# ADC_Buffer.net
KiCad netlist of a schematic drawn in Altium Designer
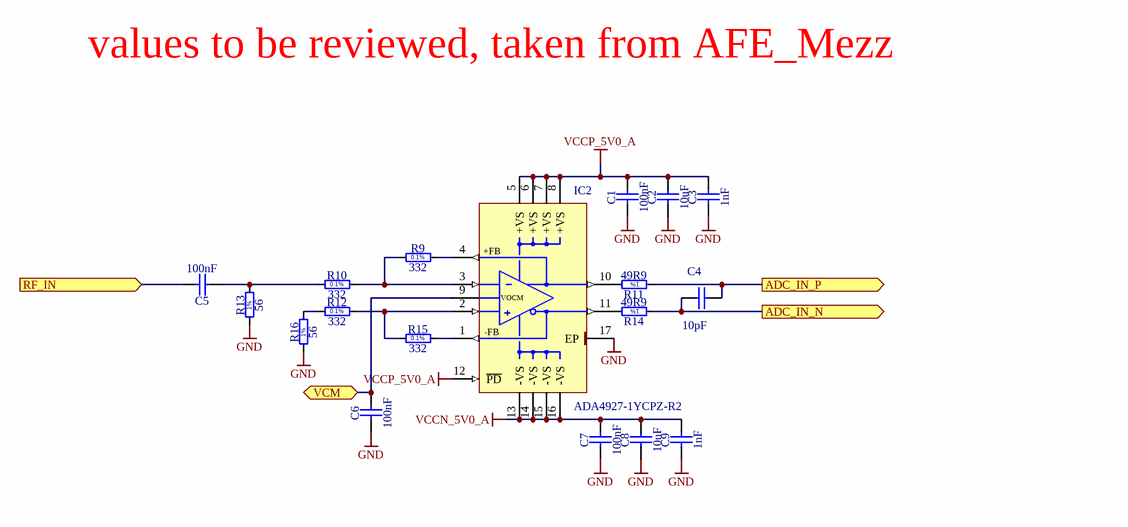
[diagram p0: ADC_Buffer.SchDoc]

(export (version "E")
  (design (tool "Eeschema 10.0.6"))
  (components
    (comp (ref "C1")
      (value "100nF")
      (footprint "CAPC1005X55N")
      (description "Non-polarised capacitor")
      (fields
        (field (name "PART NUMBER") "CC0402_100NF_16V_10%_X5R")
        (field (name "VOLTAGE") "16V")
        (field (name "AUTHOR") "CERN DEM JLC")
      )
      (libsource (lib "Capacitors") (part "Capacitor - non polarized"))
    )
    (comp (ref "C2")
      (value "10uF")
      (footprint "CAPC1608X87N")
      (description "Non-polarised capacitor")
      (fields
        (field (name "PART NUMBER") "CC0603_10UF_6.3V_20%_X5R")
        (field (name "VOLTAGE") "6.3V")
        (field (name "AUTHOR") "CERN DEM JLC")
      )
      (libsource (lib "Capacitors") (part "Capacitor - non polarized"))
    )
    (comp (ref "C3")
      (value "1nF")
      (footprint "CAPC1005X55N")
      (description "Non-polarised capacitor")
      (fields
        (field (name "PART NUMBER") "CC0402_1NF_50V_10%_X7R")
        (field (name "VOLTAGE") "50V")
        (field (name "AUTHOR") "CERN DEM JLC")
      )
      (libsource (lib "Capacitors") (part "Capacitor - non polarized"))
    )
    (comp (ref "C4")
      (value "10pF")
      (footprint "CAPC1608X87N")
      (description "Non-polarised capacitor")
      (fields
        (field (name "PART NUMBER") "CC0603_10PF_50V_5%_NP0")
        (field (name "VOLTAGE") "50V")
        (field (name "AUTHOR") "CERN DEM JLC")
      )
      (libsource (lib "Capacitors") (part "Capacitor - non polarized"))
    )
    (comp (ref "C5")
      (value "100nF")
      (footprint "CAPC1005X55N")
      (description "Non-polarised capacitor")
      (fields
        (field (name "PART NUMBER") "CC0402_100NF_16V_10%_X5R")
        (field (name "VOLTAGE") "16V")
        (field (name "AUTHOR") "CERN DEM JLC")
      )
      (libsource (lib "Capacitors") (part "Capacitor - non polarized"))
    )
    (comp (ref "C6")
      (value "100nF")
      (footprint "CAPC1005X55N")
      (description "Non-polarised capacitor")
      (fields
        (field (name "PART NUMBER") "CC0402_100NF_16V_10%_X5R")
        (field (name "VOLTAGE") "16V")
        (field (name "AUTHOR") "CERN DEM JLC")
      )
      (libsource (lib "Capacitors") (part "Capacitor - non polarized"))
    )
    (comp (ref "C7")
      (value "100nF")
      (footprint "CAPC1005X55N")
      (description "Non-polarised capacitor")
      (fields
        (field (name "PART NUMBER") "CC0402_100NF_16V_10%_X5R")
        (field (name "VOLTAGE") "16V")
        (field (name "AUTHOR") "CERN DEM JLC")
      )
      (libsource (lib "Capacitors") (part "Capacitor - non polarized"))
    )
    (comp (ref "C8")
      (value "10uF")
      (footprint "CAPC1608X87N")
      (description "Non-polarised capacitor")
      (fields
        (field (name "PART NUMBER") "CC0603_10UF_6.3V_20%_X5R")
        (field (name "VOLTAGE") "6.3V")
        (field (name "AUTHOR") "CERN DEM JLC")
      )
      (libsource (lib "Capacitors") (part "Capacitor - non polarized"))
    )
    (comp (ref "C9")
      (value "1nF")
      (footprint "CAPC1005X55N")
      (description "Non-polarised capacitor")
      (fields
        (field (name "PART NUMBER") "CC0402_1NF_50V_10%_X7R")
        (field (name "VOLTAGE") "50V")
        (field (name "AUTHOR") "CERN DEM JLC")
      )
      (libsource (lib "Capacitors") (part "Capacitor - non polarized"))
    )
    (comp (ref "IC2")
      (value "ADA4927-1YCPZ-R2")
      (footprint "QFN50P300X300X100-17N-S145")
      (description "Ultralow Distortion Current Feedback Differential ADC Driver")
      (fields (field (name "MANUFACTURER") "ANALOG DEVICES") (field (name "AUTHOR") "CERN DEM JLC"))
      (libsource (lib "ICs And Semiconductors") (part "ADA4927-1"))
    )
    (comp (ref "R9")
      (value "332")
      (footprint "RESC1608X55N")
      (description "Resistor - 0.1%")
      (fields
        (field (name "PART NUMBER") "R0603_332R_0.1%_0.063W_10PPM")
        (field (name "POWER") "0.063W")
        (field (name "AUTHOR") "CERN DEM JLC")
      )
      (libsource (lib "Resistors") (part "Resistor - 0.1%"))
    )
    (comp (ref "R10")
      (value "332")
      (footprint "RESC1608X55N")
      (description "Resistor - 0.1%")
      (fields
        (field (name "PART NUMBER") "R0603_332R_0.1%_0.063W_10PPM")
        (field (name "POWER") "0.063W")
        (field (name "AUTHOR") "CERN DEM JLC")
      )
      (libsource (lib "Resistors") (part "Resistor - 0.1%"))
    )
    (comp (ref "R11")
      (value "49R9")
      (footprint "RESC1005X40N")
      (description "Resistor - 1%")
      (fields
        (field (name "PART NUMBER") "R0402_49R9_1%_0.0625W_100PPM")
        (field (name "POWER") "0.0625W")
        (field (name "AUTHOR") "CERN DEM JLC")
      )
      (libsource (lib "Resistors") (part "Resistor - 1%"))
    )
    (comp (ref "R12")
      (value "332")
      (footprint "RESC1608X55N")
      (description "Resistor - 0.1%")
      (fields
        (field (name "PART NUMBER") "R0603_332R_0.1%_0.063W_10PPM")
        (field (name "POWER") "0.063W")
        (field (name "AUTHOR") "CERN DEM JLC")
      )
      (libsource (lib "Resistors") (part "Resistor - 0.1%"))
    )
    (comp (ref "R13")
      (value "56")
      (footprint "RESC1005X40N")
      (description "Resistor - 1%")
      (fields
        (field (name "PART NUMBER") "R0402_56R_1%_0.0625W_100PPM")
        (field (name "POWER") "0.0625W")
        (field (name "AUTHOR") "CERN DEM JLC")
      )
      (libsource (lib "Resistors") (part "Resistor - 1%"))
    )
    (comp (ref "R14")
      (value "49R9")
      (footprint "RESC1005X40N")
      (description "Resistor - 1%")
      (fields
        (field (name "PART NUMBER") "R0402_49R9_1%_0.0625W_100PPM")
        (field (name "POWER") "0.0625W")
        (field (name "AUTHOR") "CERN DEM JLC")
      )
      (libsource (lib "Resistors") (part "Resistor - 1%"))
    )
    (comp (ref "R15")
      (value "332")
      (footprint "RESC1608X55N")
      (description "Resistor - 0.1%")
      (fields
        (field (name "PART NUMBER") "R0603_332R_0.1%_0.063W_10PPM")
        (field (name "POWER") "0.063W")
        (field (name "AUTHOR") "CERN DEM JLC")
      )
      (libsource (lib "Resistors") (part "Resistor - 0.1%"))
    )
    (comp (ref "R16")
      (value "56")
      (footprint "RESC1005X40N")
      (description "Resistor - 1%")
      (fields
        (field (name "PART NUMBER") "R0402_56R_1%_0.0625W_100PPM")
        (field (name "POWER") "0.0625W")
        (field (name "AUTHOR") "CERN DEM JLC")
      )
      (libsource (lib "Resistors") (part "Resistor - 1%"))
    )
  )
  (nets
    (net (code "1") (name "/ADC_IN_N") (class "Default")
      (node (ref "C4") (pin "1") (pinfunction "1_1") (pintype "passive"))
      (node (ref "R14") (pin "1") (pinfunction "1_1") (pintype "passive"))
    )
    (net (code "2") (name "/ADC_IN_P") (class "Default")
      (node (ref "C4") (pin "2") (pinfunction "2_2") (pintype "passive"))
      (node (ref "R11") (pin "1") (pinfunction "1_1") (pintype "passive"))
    )
    (net (code "3") (name "/RF_IN") (class "Default")
      (node (ref "C5") (pin "2") (pinfunction "2_2") (pintype "passive"))
    )
    (net (code "4") (name "/VCM") (class "Default")
      (node (ref "C6") (pin "2") (pinfunction "2_2") (pintype "passive"))
      (node (ref "IC2") (pin "9") (pinfunction "VOCM_9") (pintype "passive"))
    )
    (net (code "5") (name "GND") (class "Default")
      (node (ref "C1") (pin "1") (pinfunction "1_1") (pintype "passive"))
      (node (ref "C2") (pin "1") (pinfunction "1_1") (pintype "passive"))
      (node (ref "C3") (pin "1") (pinfunction "1_1") (pintype "passive"))
      (node (ref "C6") (pin "1") (pinfunction "1_1") (pintype "passive"))
      (node (ref "C7") (pin "1") (pinfunction "1_1") (pintype "passive"))
      (node (ref "C8") (pin "1") (pinfunction "1_1") (pintype "passive"))
      (node (ref "C9") (pin "1") (pinfunction "1_1") (pintype "passive"))
      (node (ref "IC2") (pin "17") (pinfunction "EP_17") (pintype "power_in"))
      (node (ref "R13") (pin "1") (pinfunction "1_1") (pintype "passive"))
      (node (ref "R16") (pin "1") (pinfunction "1_1") (pintype "passive"))
    )
    (net (code "6") (name "Net-(C5-Pad1)") (class "Default")
      (node (ref "C5") (pin "1") (pinfunction "1_1") (pintype "passive"))
      (node (ref "R10") (pin "1") (pinfunction "1_1") (pintype "passive"))
      (node (ref "R13") (pin "2") (pinfunction "2_2") (pintype "passive"))
    )
    (net (code "7") (name "Net-(IC2-+FB)") (class "Default")
      (node (ref "IC2") (pin "4") (pinfunction "+FB_4") (pintype "output"))
      (node (ref "R9") (pin "2") (pinfunction "2_2") (pintype "passive"))
    )
    (net (code "8") (name "Net-(IC2-+IN)") (class "Default")
      (node (ref "IC2") (pin "2") (pinfunction "+IN_2") (pintype "input"))
      (node (ref "R12") (pin "2") (pinfunction "2_2") (pintype "passive"))
      (node (ref "R15") (pin "1") (pinfunction "1_1") (pintype "passive"))
    )
    (net (code "9") (name "Net-(IC2-+OUT)") (class "Default")
      (node (ref "IC2") (pin "10") (pinfunction "+OUT_10") (pintype "output"))
      (node (ref "R11") (pin "2") (pinfunction "2_2") (pintype "passive"))
    )
    (net (code "10") (name "Net-(IC2--FB)") (class "Default")
      (node (ref "IC2") (pin "1") (pinfunction "-FB_1") (pintype "output"))
      (node (ref "R15") (pin "2") (pinfunction "2_2") (pintype "passive"))
    )
    (net (code "11") (name "Net-(IC2--IN)") (class "Default")
      (node (ref "IC2") (pin "3") (pinfunction "-IN_3") (pintype "input"))
      (node (ref "R10") (pin "2") (pinfunction "2_2") (pintype "passive"))
      (node (ref "R9") (pin "1") (pinfunction "1_1") (pintype "passive"))
    )
    (net (code "12") (name "Net-(IC2--OUT)") (class "Default")
      (node (ref "IC2") (pin "11") (pinfunction "-OUT_11") (pintype "output"))
      (node (ref "R14") (pin "2") (pinfunction "2_2") (pintype "passive"))
    )
    (net (code "13") (name "Net-(R12-Pad1)") (class "Default")
      (node (ref "R12") (pin "1") (pinfunction "1_1") (pintype "passive"))
      (node (ref "R16") (pin "2") (pinfunction "2_2") (pintype "passive"))
    )
    (net (code "14") (name "VCCN_5V0_A") (class "Default")
      (node (ref "C7") (pin "2") (pinfunction "2_2") (pintype "passive"))
      (node (ref "C8") (pin "2") (pinfunction "2_2") (pintype "passive"))
      (node (ref "C9") (pin "2") (pinfunction "2_2") (pintype "passive"))
      (node (ref "IC2") (pin "13") (pinfunction "-VS_13") (pintype "power_in"))
      (node (ref "IC2") (pin "14") (pinfunction "-VS_14") (pintype "power_in"))
      (node (ref "IC2") (pin "15") (pinfunction "-VS_15") (pintype "power_in"))
      (node (ref "IC2") (pin "16") (pinfunction "-VS_16") (pintype "power_in"))
    )
    (net (code "15") (name "VCCP_5V0_A") (class "Default")
      (node (ref "C1") (pin "2") (pinfunction "2_2") (pintype "passive"))
      (node (ref "C2") (pin "2") (pinfunction "2_2") (pintype "passive"))
      (node (ref "C3") (pin "2") (pinfunction "2_2") (pintype "passive"))
      (node (ref "IC2") (pin "12") (pinfunction "~{PD}_12") (pintype "input"))
      (node (ref "IC2") (pin "5") (pinfunction "+VS_5") (pintype "power_in"))
      (node (ref "IC2") (pin "6") (pinfunction "+VS_6") (pintype "power_in"))
      (node (ref "IC2") (pin "7") (pinfunction "+VS_7") (pintype "power_in"))
      (node (ref "IC2") (pin "8") (pinfunction "+VS_8") (pintype "power_in"))
    )
  )
)
